# VCU_1_2.net
KiCad netlist of a schematic drawn in Altium Designer
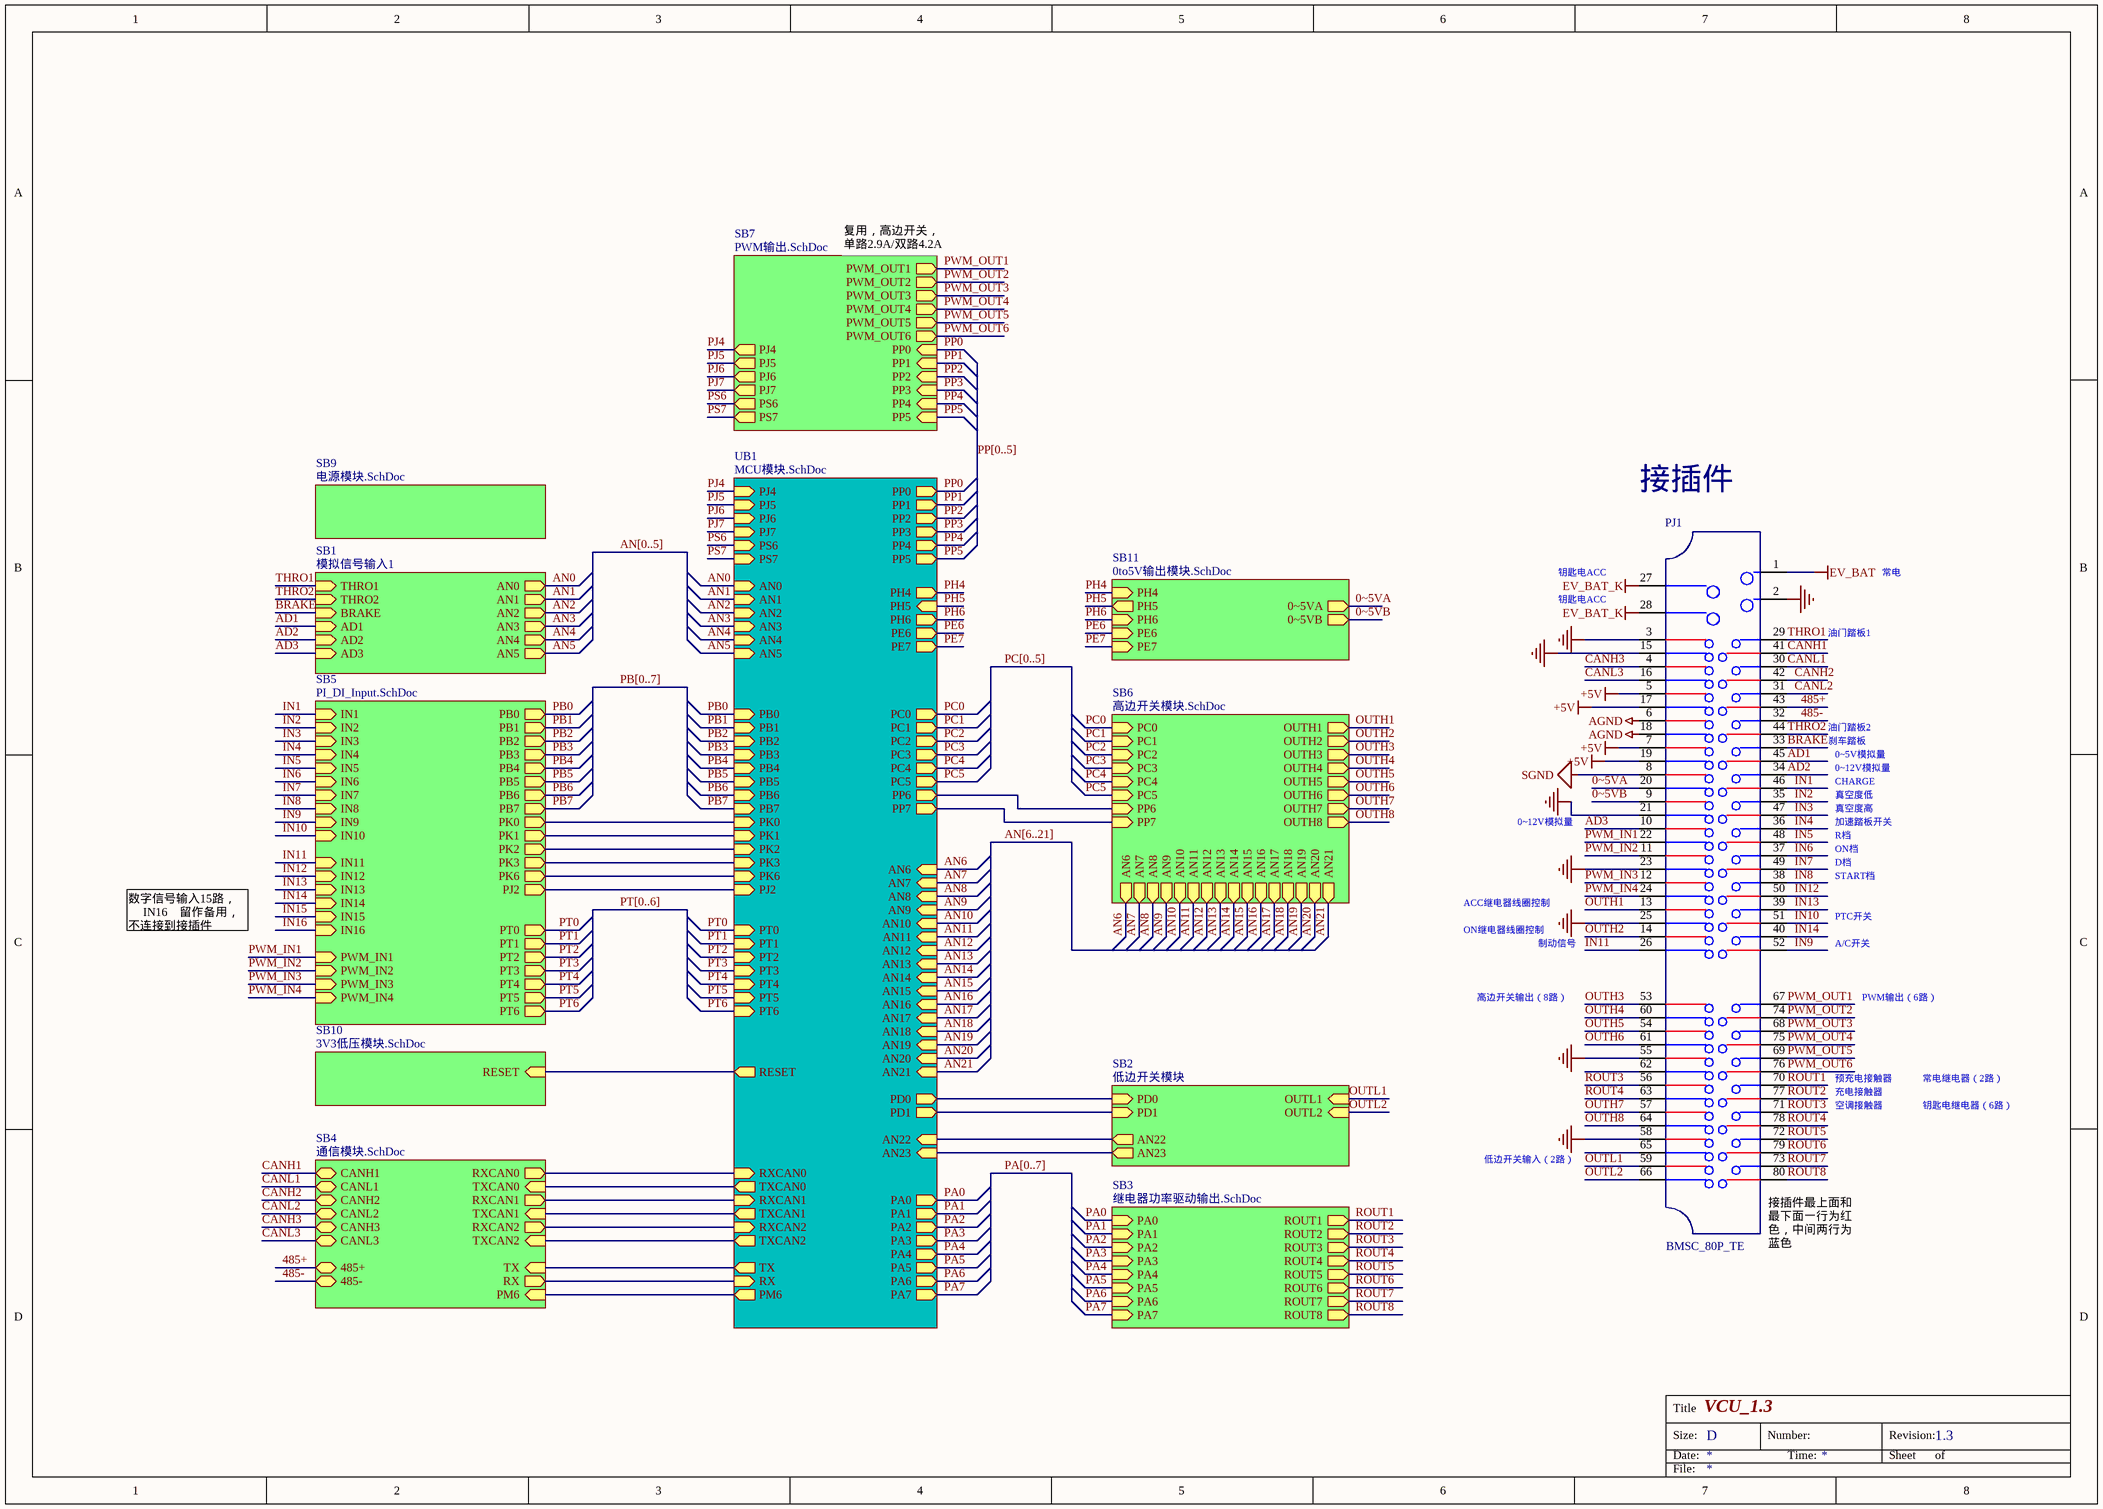
[diagram p0: VCU_1_2.SchDoc]

(export (version "E")
  (design (tool "Eeschema 10.0.6"))
  (components
    (comp (ref "PJ1") (value "BMSC_80P_TE") (footprint "BMSC_80P") (libsource (lib "BMS") (part "BMSC_80P")))
  )
  (nets
    (net (code "1") (name "+5V") (class "Default")
      (node (ref "PJ1") (pin "17") (pinfunction "68_17") (pintype "passive"))
      (node (ref "PJ1") (pin "19") (pinfunction "70_19") (pintype "passive"))
      (node (ref "PJ1") (pin "5") (pinfunction "56_5") (pintype "passive"))
      (node (ref "PJ1") (pin "7") (pinfunction "58_7") (pintype "passive"))
    )
    (net (code "2") (name "/0~5VA") (class "Default")
      (node (ref "PJ1") (pin "20") (pinfunction "71_20") (pintype "passive"))
    )
    (net (code "3") (name "/0~5VB") (class "Default")
      (node (ref "PJ1") (pin "9") (pinfunction "60_9") (pintype "passive"))
    )
    (net (code "4") (name "/485+") (class "Default")
      (node (ref "PJ1") (pin "43") (pinfunction "94_43") (pintype "passive"))
    )
    (net (code "5") (name "/485-") (class "Default")
      (node (ref "PJ1") (pin "32") (pinfunction "83_32") (pintype "passive"))
    )
    (net (code "6") (name "/AD1") (class "Default")
      (node (ref "PJ1") (pin "45") (pinfunction "96_45") (pintype "passive"))
    )
    (net (code "7") (name "/AD2") (class "Default")
      (node (ref "PJ1") (pin "34") (pinfunction "85_34") (pintype "passive"))
    )
    (net (code "8") (name "/AD3") (class "Default")
      (node (ref "PJ1") (pin "10") (pinfunction "61_10") (pintype "passive"))
    )
    (net (code "35") (name "/BRAKE") (class "Default")
      (node (ref "PJ1") (pin "33") (pinfunction "84_33") (pintype "passive"))
    )
    (net (code "36") (name "/CANH1") (class "Default")
      (node (ref "PJ1") (pin "41") (pinfunction "92_41") (pintype "passive"))
    )
    (net (code "37") (name "/CANH2") (class "Default")
      (node (ref "PJ1") (pin "42") (pinfunction "93_42") (pintype "passive"))
    )
    (net (code "38") (name "/CANH3") (class "Default")
      (node (ref "PJ1") (pin "4") (pinfunction "55_4") (pintype "passive"))
    )
    (net (code "39") (name "/CANL1") (class "Default")
      (node (ref "PJ1") (pin "30") (pinfunction "81_30") (pintype "passive"))
    )
    (net (code "40") (name "/CANL2") (class "Default")
      (node (ref "PJ1") (pin "31") (pinfunction "82_31") (pintype "passive"))
    )
    (net (code "41") (name "/CANL3") (class "Default")
      (node (ref "PJ1") (pin "16") (pinfunction "67_16") (pintype "passive"))
    )
    (net (code "42") (name "/IN1") (class "Default")
      (node (ref "PJ1") (pin "46") (pinfunction "97_46") (pintype "passive"))
    )
    (net (code "43") (name "/IN2") (class "Default")
      (node (ref "PJ1") (pin "35") (pinfunction "86_35") (pintype "passive"))
    )
    (net (code "44") (name "/IN3") (class "Default")
      (node (ref "PJ1") (pin "47") (pinfunction "98_47") (pintype "passive"))
    )
    (net (code "45") (name "/IN4") (class "Default")
      (node (ref "PJ1") (pin "36") (pinfunction "87_36") (pintype "passive"))
    )
    (net (code "46") (name "/IN5") (class "Default")
      (node (ref "PJ1") (pin "48") (pinfunction "99_48") (pintype "passive"))
    )
    (net (code "47") (name "/IN6") (class "Default")
      (node (ref "PJ1") (pin "37") (pinfunction "88_37") (pintype "passive"))
    )
    (net (code "48") (name "/IN7") (class "Default")
      (node (ref "PJ1") (pin "49") (pinfunction "100_49") (pintype "passive"))
    )
    (net (code "49") (name "/IN8") (class "Default")
      (node (ref "PJ1") (pin "38") (pinfunction "89_38") (pintype "passive"))
    )
    (net (code "50") (name "/IN9") (class "Default")
      (node (ref "PJ1") (pin "52") (pinfunction "103_52") (pintype "passive"))
    )
    (net (code "51") (name "/IN10") (class "Default")
      (node (ref "PJ1") (pin "51") (pinfunction "102_51") (pintype "passive"))
    )
    (net (code "52") (name "/IN11") (class "Default")
      (node (ref "PJ1") (pin "26") (pinfunction "77_26") (pintype "passive"))
    )
    (net (code "53") (name "/IN12") (class "Default")
      (node (ref "PJ1") (pin "50") (pinfunction "101_50") (pintype "passive"))
    )
    (net (code "54") (name "/IN13") (class "Default")
      (node (ref "PJ1") (pin "39") (pinfunction "90_39") (pintype "passive"))
    )
    (net (code "55") (name "/IN14") (class "Default")
      (node (ref "PJ1") (pin "40") (pinfunction "91_40") (pintype "passive"))
    )
    (net (code "58") (name "/OUTH1") (class "Default")
      (node (ref "PJ1") (pin "13") (pinfunction "64_13") (pintype "passive"))
    )
    (net (code "59") (name "/OUTH2") (class "Default")
      (node (ref "PJ1") (pin "14") (pinfunction "65_14") (pintype "passive"))
    )
    (net (code "60") (name "/OUTH3") (class "Default")
      (node (ref "PJ1") (pin "53") (pinfunction "104_53") (pintype "passive"))
    )
    (net (code "61") (name "/OUTH4") (class "Default")
      (node (ref "PJ1") (pin "60") (pinfunction "111_60") (pintype "passive"))
    )
    (net (code "62") (name "/OUTH5") (class "Default")
      (node (ref "PJ1") (pin "54") (pinfunction "105_54") (pintype "passive"))
    )
    (net (code "63") (name "/OUTH6") (class "Default")
      (node (ref "PJ1") (pin "61") (pinfunction "112_61") (pintype "passive"))
    )
    (net (code "64") (name "/OUTH7") (class "Default")
      (node (ref "PJ1") (pin "57") (pinfunction "108_57") (pintype "passive"))
    )
    (net (code "65") (name "/OUTH8") (class "Default")
      (node (ref "PJ1") (pin "64") (pinfunction "115_64") (pintype "passive"))
    )
    (net (code "66") (name "/OUTL1") (class "Default")
      (node (ref "PJ1") (pin "59") (pinfunction "110_59") (pintype "passive"))
    )
    (net (code "67") (name "/OUTL2") (class "Default")
      (node (ref "PJ1") (pin "66") (pinfunction "117_66") (pintype "passive"))
    )
    (net (code "130") (name "/PWM_IN1") (class "Default")
      (node (ref "PJ1") (pin "22") (pinfunction "73_22") (pintype "passive"))
    )
    (net (code "131") (name "/PWM_IN2") (class "Default")
      (node (ref "PJ1") (pin "11") (pinfunction "62_11") (pintype "passive"))
    )
    (net (code "132") (name "/PWM_IN3") (class "Default")
      (node (ref "PJ1") (pin "12") (pinfunction "63_12") (pintype "passive"))
    )
    (net (code "133") (name "/PWM_IN4") (class "Default")
      (node (ref "PJ1") (pin "24") (pinfunction "75_24") (pintype "passive"))
    )
    (net (code "134") (name "/PWM_OUT1") (class "Default")
      (node (ref "PJ1") (pin "67") (pinfunction "118_67") (pintype "passive"))
    )
    (net (code "135") (name "/PWM_OUT2") (class "Default")
      (node (ref "PJ1") (pin "74") (pinfunction "125_74") (pintype "passive"))
    )
    (net (code "136") (name "/PWM_OUT3") (class "Default")
      (node (ref "PJ1") (pin "68") (pinfunction "119_68") (pintype "passive"))
    )
    (net (code "137") (name "/PWM_OUT4") (class "Default")
      (node (ref "PJ1") (pin "75") (pinfunction "126_75") (pintype "passive"))
    )
    (net (code "138") (name "/PWM_OUT5") (class "Default")
      (node (ref "PJ1") (pin "69") (pinfunction "120_69") (pintype "passive"))
    )
    (net (code "139") (name "/PWM_OUT6") (class "Default")
      (node (ref "PJ1") (pin "76") (pinfunction "127_76") (pintype "passive"))
    )
    (net (code "141") (name "/ROUT1") (class "Default")
      (node (ref "PJ1") (pin "70") (pinfunction "121_70") (pintype "passive"))
    )
    (net (code "142") (name "/ROUT2") (class "Default")
      (node (ref "PJ1") (pin "77") (pinfunction "128_77") (pintype "passive"))
    )
    (net (code "143") (name "/ROUT3") (class "Default")
      (node (ref "PJ1") (pin "56") (pinfunction "107_56") (pintype "passive"))
      (node (ref "PJ1") (pin "71") (pinfunction "122_71") (pintype "passive"))
    )
    (net (code "144") (name "/ROUT4") (class "Default")
      (node (ref "PJ1") (pin "63") (pinfunction "114_63") (pintype "passive"))
      (node (ref "PJ1") (pin "78") (pinfunction "129_78") (pintype "passive"))
    )
    (net (code "145") (name "/ROUT5") (class "Default")
      (node (ref "PJ1") (pin "72") (pinfunction "123_72") (pintype "passive"))
    )
    (net (code "146") (name "/ROUT6") (class "Default")
      (node (ref "PJ1") (pin "79") (pinfunction "130_79") (pintype "passive"))
    )
    (net (code "147") (name "/ROUT7") (class "Default")
      (node (ref "PJ1") (pin "73") (pinfunction "124_73") (pintype "passive"))
    )
    (net (code "148") (name "/ROUT8") (class "Default")
      (node (ref "PJ1") (pin "80") (pinfunction "131_80") (pintype "passive"))
    )
    (net (code "153") (name "/THRO1") (class "Default")
      (node (ref "PJ1") (pin "29") (pinfunction "80_29") (pintype "passive"))
    )
    (net (code "154") (name "/THRO2") (class "Default")
      (node (ref "PJ1") (pin "44") (pinfunction "95_44") (pintype "passive"))
    )
    (net (code "159") (name "AGND") (class "Default")
      (node (ref "PJ1") (pin "18") (pinfunction "69_18") (pintype "passive"))
      (node (ref "PJ1") (pin "6") (pinfunction "57_6") (pintype "passive"))
    )
    (net (code "160") (name "EV_BAT") (class "Default")
      (node (ref "PJ1") (pin "1") (pinfunction "52_1") (pintype "passive"))
    )
    (net (code "161") (name "EV_BAT_K") (class "Default")
      (node (ref "PJ1") (pin "27") (pinfunction "78_27") (pintype "passive"))
      (node (ref "PJ1") (pin "28") (pinfunction "79_28") (pintype "passive"))
    )
    (net (code "162") (name "GND") (class "Default")
      (node (ref "PJ1") (pin "15") (pinfunction "66_15") (pintype "passive"))
      (node (ref "PJ1") (pin "2") (pinfunction "53_2") (pintype "passive"))
      (node (ref "PJ1") (pin "21") (pinfunction "72_21") (pintype "passive"))
      (node (ref "PJ1") (pin "23") (pinfunction "74_23") (pintype "passive"))
      (node (ref "PJ1") (pin "25") (pinfunction "76_25") (pintype "passive"))
      (node (ref "PJ1") (pin "3") (pinfunction "54_3") (pintype "passive"))
      (node (ref "PJ1") (pin "55") (pinfunction "106_55") (pintype "passive"))
      (node (ref "PJ1") (pin "58") (pinfunction "109_58") (pintype "passive"))
    )
    (net (code "163") (name "SGND") (class "Default")
      (node (ref "PJ1") (pin "8") (pinfunction "59_8") (pintype "passive"))
    )
    (net (code "164") (name "unconnected-(PJ1-113-Pad62)") (class "Default")
      (node (ref "PJ1") (pin "62") (pinfunction "113_62") (pintype "passive"))
    )
    (net (code "165") (name "unconnected-(PJ1-116-Pad65)") (class "Default")
      (node (ref "PJ1") (pin "65") (pinfunction "116_65") (pintype "passive"))
    )
  )
)
